# Force.net
KiCad netlist of a schematic drawn in Altium Designer
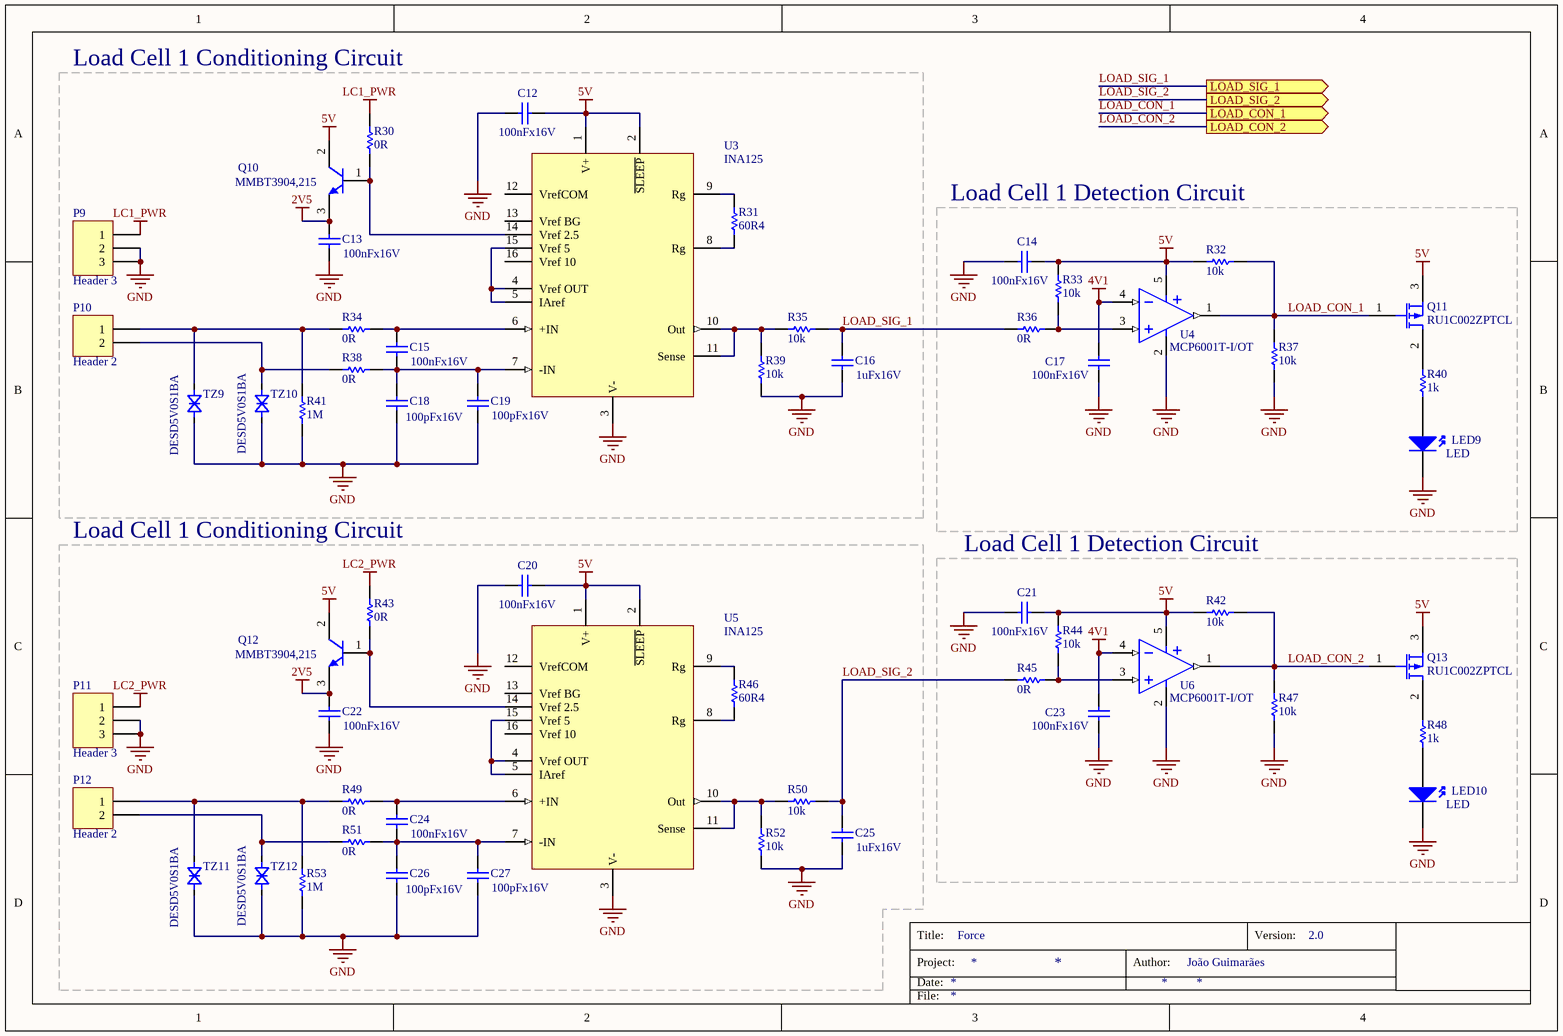
[diagram p0: Force.SchDoc]

(export (version "E")
  (design (tool "Eeschema 10.0.6"))
  (components
    (comp (ref "C12")
      (value "100nFx16V")
      (footprint "DISC-0805")
      (description "Capacitor")
      (libsource (lib "IntLib") (part "Cap"))
    )
    (comp (ref "C13")
      (value "100nFx16V")
      (footprint "DISC-0805")
      (description "Capacitor")
      (libsource (lib "IntLib") (part "Cap"))
    )
    (comp (ref "C14")
      (value "100nFx16V")
      (footprint "DISC-0805")
      (description "Capacitor")
      (libsource (lib "IntLib") (part "Cap"))
    )
    (comp (ref "C15")
      (value "100nFx16V")
      (footprint "DISC-0805")
      (description "Capacitor")
      (libsource (lib "IntLib") (part "Cap"))
    )
    (comp (ref "C16")
      (value "1uFx16V")
      (footprint "DISC-0805")
      (description "Capacitor")
      (libsource (lib "IntLib") (part "Cap"))
    )
    (comp (ref "C17")
      (value "100nFx16V")
      (footprint "DISC-0805")
      (description "Capacitor")
      (libsource (lib "IntLib") (part "Cap"))
    )
    (comp (ref "C18")
      (value "100pFx16V")
      (footprint "DISC-0805")
      (description "Capacitor")
      (libsource (lib "IntLib") (part "Cap"))
    )
    (comp (ref "C19")
      (value "100pFx16V")
      (footprint "DISC-0805")
      (description "Capacitor")
      (libsource (lib "IntLib") (part "Cap"))
    )
    (comp (ref "C20")
      (value "100nFx16V")
      (footprint "DISC-0805")
      (description "Capacitor")
      (libsource (lib "IntLib") (part "Cap"))
    )
    (comp (ref "C21")
      (value "100nFx16V")
      (footprint "DISC-0805")
      (description "Capacitor")
      (libsource (lib "IntLib") (part "Cap"))
    )
    (comp (ref "C22")
      (value "100nFx16V")
      (footprint "DISC-0805")
      (description "Capacitor")
      (libsource (lib "IntLib") (part "Cap"))
    )
    (comp (ref "C23")
      (value "100nFx16V")
      (footprint "DISC-0805")
      (description "Capacitor")
      (libsource (lib "IntLib") (part "Cap"))
    )
    (comp (ref "C24")
      (value "100nFx16V")
      (footprint "DISC-0805")
      (description "Capacitor")
      (libsource (lib "IntLib") (part "Cap"))
    )
    (comp (ref "C25")
      (value "1uFx16V")
      (footprint "DISC-0805")
      (description "Capacitor")
      (libsource (lib "IntLib") (part "Cap"))
    )
    (comp (ref "C26")
      (value "100pFx16V")
      (footprint "DISC-0805")
      (description "Capacitor")
      (libsource (lib "IntLib") (part "Cap"))
    )
    (comp (ref "C27")
      (value "100pFx16V")
      (footprint "DISC-0805")
      (description "Capacitor")
      (libsource (lib "IntLib") (part "Cap"))
    )
    (comp (ref "LED9") (value "LED") (footprint "DISC-LED-0.1-PTH") (libsource (lib "IntLib") (part "LED")))
    (comp (ref "LED10") (value "LED") (footprint "DISC-LED-0.1-PTH") (libsource (lib "IntLib") (part "LED")))
    (comp (ref "P9")
      (value "Header 3")
      (footprint "CON-FLEXWIRE-0.5MM2-1X3")
      (description "Header, 3-Pin")
      (fields (field (name "PUBLISHER") "Altium Limited"))
      (libsource (lib "IntLib") (part "Header 3"))
    )
    (comp (ref "P10")
      (value "Header 2")
      (footprint "CON-BORNE-2")
      (description "Header, 2-Pin")
      (fields (field (name "PUBLISHER") "Altium Limited"))
      (libsource (lib "IntLib") (part "Header 2"))
    )
    (comp (ref "P11")
      (value "Header 3")
      (footprint "CON-FLEXWIRE-0.5MM2-1X3")
      (description "Header, 3-Pin")
      (fields (field (name "PUBLISHER") "Altium Limited"))
      (libsource (lib "IntLib") (part "Header 3"))
    )
    (comp (ref "P12")
      (value "Header 2")
      (footprint "CON-BORNE-2")
      (description "Header, 2-Pin")
      (fields (field (name "PUBLISHER") "Altium Limited"))
      (libsource (lib "IntLib") (part "Header 2"))
    )
    (comp (ref "Q10")
      (value "MMBT3904,215")
      (footprint "DISC-SOT-23")
      (description "NPN Bipolar Transistor")
      (fields (field (name "PUBLISHER") "Altium Limited"))
      (libsource (lib "IntLib") (part "Transistor-NPN"))
    )
    (comp (ref "Q11")
      (value "RU1C002ZPTCL")
      (footprint "DISC-SOT-23")
      (description "P-Channel MOSFET")
      (libsource (lib "IntLib") (part "Transistor-PMOS"))
    )
    (comp (ref "Q12")
      (value "MMBT3904,215")
      (footprint "DISC-SOT-23")
      (description "NPN Bipolar Transistor")
      (fields (field (name "PUBLISHER") "Altium Limited"))
      (libsource (lib "IntLib") (part "Transistor-NPN"))
    )
    (comp (ref "Q13")
      (value "RU1C002ZPTCL")
      (footprint "DISC-SOT-23")
      (description "P-Channel MOSFET")
      (libsource (lib "IntLib") (part "Transistor-PMOS"))
    )
    (comp (ref "R30")
      (value "0R")
      (footprint "DISC-0805")
      (description "Resistor")
      (libsource (lib "IntLib") (part "Res"))
    )
    (comp (ref "R31")
      (value "60R4")
      (footprint "DISC-0805")
      (description "Resistor")
      (libsource (lib "IntLib") (part "Res"))
    )
    (comp (ref "R32")
      (value "10k")
      (footprint "DISC-0805")
      (description "Resistor")
      (libsource (lib "IntLib") (part "Res"))
    )
    (comp (ref "R33")
      (value "10k")
      (footprint "DISC-0805")
      (description "Resistor")
      (libsource (lib "IntLib") (part "Res"))
    )
    (comp (ref "R34")
      (value "0R")
      (footprint "DISC-0805")
      (description "Resistor")
      (libsource (lib "IntLib") (part "Res"))
    )
    (comp (ref "R35")
      (value "10k")
      (footprint "DISC-0805")
      (description "Resistor")
      (libsource (lib "IntLib") (part "Res"))
    )
    (comp (ref "R36")
      (value "0R")
      (footprint "DISC-0805")
      (description "Resistor")
      (libsource (lib "IntLib") (part "Res"))
    )
    (comp (ref "R37")
      (value "10k")
      (footprint "DISC-0805")
      (description "Resistor")
      (libsource (lib "IntLib") (part "Res"))
    )
    (comp (ref "R38")
      (value "0R")
      (footprint "DISC-0805")
      (description "Resistor")
      (libsource (lib "IntLib") (part "Res"))
    )
    (comp (ref "R39")
      (value "10k")
      (footprint "DISC-0805")
      (description "Resistor")
      (libsource (lib "IntLib") (part "Res"))
    )
    (comp (ref "R40")
      (value "1k")
      (footprint "DISC-0805")
      (description "Resistor")
      (libsource (lib "IntLib") (part "Res"))
    )
    (comp (ref "R41")
      (value "1M")
      (footprint "DISC-0805")
      (description "Resistor")
      (libsource (lib "IntLib") (part "Res"))
    )
    (comp (ref "R42")
      (value "10k")
      (footprint "DISC-0805")
      (description "Resistor")
      (libsource (lib "IntLib") (part "Res"))
    )
    (comp (ref "R43")
      (value "0R")
      (footprint "DISC-0805")
      (description "Resistor")
      (libsource (lib "IntLib") (part "Res"))
    )
    (comp (ref "R44")
      (value "10k")
      (footprint "DISC-0805")
      (description "Resistor")
      (libsource (lib "IntLib") (part "Res"))
    )
    (comp (ref "R45")
      (value "0R")
      (footprint "DISC-0805")
      (description "Resistor")
      (libsource (lib "IntLib") (part "Res"))
    )
    (comp (ref "R46")
      (value "60R4")
      (footprint "DISC-0805")
      (description "Resistor")
      (libsource (lib "IntLib") (part "Res"))
    )
    (comp (ref "R47")
      (value "10k")
      (footprint "DISC-0805")
      (description "Resistor")
      (libsource (lib "IntLib") (part "Res"))
    )
    (comp (ref "R48")
      (value "1k")
      (footprint "DISC-0805")
      (description "Resistor")
      (libsource (lib "IntLib") (part "Res"))
    )
    (comp (ref "R49")
      (value "0R")
      (footprint "DISC-0805")
      (description "Resistor")
      (libsource (lib "IntLib") (part "Res"))
    )
    (comp (ref "R50")
      (value "10k")
      (footprint "DISC-0805")
      (description "Resistor")
      (libsource (lib "IntLib") (part "Res"))
    )
    (comp (ref "R51")
      (value "0R")
      (footprint "DISC-0805")
      (description "Resistor")
      (libsource (lib "IntLib") (part "Res"))
    )
    (comp (ref "R52")
      (value "10k")
      (footprint "DISC-0805")
      (description "Resistor")
      (libsource (lib "IntLib") (part "Res"))
    )
    (comp (ref "R53")
      (value "1M")
      (footprint "DISC-0805")
      (description "Resistor")
      (libsource (lib "IntLib") (part "Res"))
    )
    (comp (ref "TZ9")
      (value "DESD5V0S1BA")
      (footprint "DISC-SOD-323")
      (description "TVZ-Bi-Directional")
      (libsource (lib "IntLib") (part "TVZ-Bi-Directional"))
    )
    (comp (ref "TZ10")
      (value "DESD5V0S1BA")
      (footprint "DISC-SOD-323")
      (description "TVZ-Bi-Directional")
      (libsource (lib "IntLib") (part "TVZ-Bi-Directional"))
    )
    (comp (ref "TZ11")
      (value "DESD5V0S1BA")
      (footprint "DISC-SOD-323")
      (description "TVZ-Bi-Directional")
      (libsource (lib "IntLib") (part "TVZ-Bi-Directional"))
    )
    (comp (ref "TZ12")
      (value "DESD5V0S1BA")
      (footprint "DISC-SOD-323")
      (description "TVZ-Bi-Directional")
      (libsource (lib "IntLib") (part "TVZ-Bi-Directional"))
    )
    (comp (ref "U3")
      (value "INA125")
      (footprint "CI-SOIC-16")
      (description "INSTRUMENTATION AMPLIFIER With Precision Voltage Reference")
      (libsource (lib "IntLib") (part "INA125P"))
    )
    (comp (ref "U4")
      (value "MCP6001T-I/OT")
      (footprint "CI-SOT-23-5")
      (description "Operational Amplifiers - Op Amps Single 1.8V 1MHz")
      (libsource (lib "IntLib") (part "MCP6001T-I/OT"))
    )
    (comp (ref "U5")
      (value "INA125")
      (footprint "CI-SOIC-16")
      (description "INSTRUMENTATION AMPLIFIER With Precision Voltage Reference")
      (libsource (lib "IntLib") (part "INA125P"))
    )
    (comp (ref "U6")
      (value "MCP6001T-I/OT")
      (footprint "CI-SOT-23-5")
      (description "Operational Amplifiers - Op Amps Single 1.8V 1MHz")
      (libsource (lib "IntLib") (part "MCP6001T-I/OT"))
    )
  )
  (nets
    (net (code "1") (name "/LOAD_CON_1") (class "Default")
      (node (ref "Q11") (pin "1") (pinfunction "G_1") (pintype "passive"))
      (node (ref "R32") (pin "2") (pinfunction "2_2") (pintype "passive"))
      (node (ref "R37") (pin "1") (pinfunction "1_1") (pintype "passive"))
      (node (ref "U4") (pin "1") (pinfunction "Out_1") (pintype "output"))
    )
    (net (code "2") (name "/LOAD_CON_2") (class "Default")
      (node (ref "Q13") (pin "1") (pinfunction "G_1") (pintype "passive"))
      (node (ref "R42") (pin "2") (pinfunction "2_2") (pintype "passive"))
      (node (ref "R47") (pin "1") (pinfunction "1_1") (pintype "passive"))
      (node (ref "U6") (pin "1") (pinfunction "Out_1") (pintype "output"))
    )
    (net (code "3") (name "/LOAD_SIG_1") (class "Default")
      (node (ref "C16") (pin "2") (pinfunction "2_2") (pintype "passive"))
      (node (ref "R35") (pin "2") (pinfunction "2_2") (pintype "passive"))
      (node (ref "R36") (pin "1") (pinfunction "1_1") (pintype "passive"))
    )
    (net (code "4") (name "/LOAD_SIG_2") (class "Default")
      (node (ref "C25") (pin "2") (pinfunction "2_2") (pintype "passive"))
      (node (ref "R45") (pin "1") (pinfunction "1_1") (pintype "passive"))
      (node (ref "R50") (pin "2") (pinfunction "2_2") (pintype "passive"))
    )
    (net (code "5") (name "2V5") (class "Default")
      (node (ref "C13") (pin "2") (pinfunction "2_2") (pintype "passive"))
      (node (ref "C22") (pin "2") (pinfunction "2_2") (pintype "passive"))
      (node (ref "Q10") (pin "3") (pinfunction "E_3") (pintype "passive"))
      (node (ref "Q12") (pin "3") (pinfunction "E_3") (pintype "passive"))
    )
    (net (code "6") (name "4V1") (class "Default")
      (node (ref "C17") (pin "2") (pinfunction "2_2") (pintype "passive"))
      (node (ref "C23") (pin "2") (pinfunction "2_2") (pintype "passive"))
      (node (ref "U4") (pin "4") (pinfunction "IN-_4") (pintype "input"))
      (node (ref "U6") (pin "4") (pinfunction "IN-_4") (pintype "input"))
    )
    (net (code "7") (name "5V") (class "Default")
      (node (ref "C12") (pin "1") (pinfunction "1_1") (pintype "passive"))
      (node (ref "C14") (pin "2") (pinfunction "2_2") (pintype "passive"))
      (node (ref "C20") (pin "1") (pinfunction "1_1") (pintype "passive"))
      (node (ref "C21") (pin "2") (pinfunction "2_2") (pintype "passive"))
      (node (ref "Q10") (pin "2") (pinfunction "C_2") (pintype "passive"))
      (node (ref "Q11") (pin "3") (pinfunction "S_3") (pintype "passive"))
      (node (ref "Q12") (pin "2") (pinfunction "C_2") (pintype "passive"))
      (node (ref "Q13") (pin "3") (pinfunction "S_3") (pintype "passive"))
      (node (ref "R32") (pin "1") (pinfunction "1_1") (pintype "passive"))
      (node (ref "R33") (pin "1") (pinfunction "1_1") (pintype "passive"))
      (node (ref "R42") (pin "1") (pinfunction "1_1") (pintype "passive"))
      (node (ref "R44") (pin "1") (pinfunction "1_1") (pintype "passive"))
      (node (ref "U3") (pin "1") (pinfunction "V+_1") (pintype "power_in"))
      (node (ref "U3") (pin "2") (pinfunction "~{SLEEP}_2") (pintype "passive"))
      (node (ref "U4") (pin "5") (pinfunction "V+_5") (pintype "power_in"))
      (node (ref "U5") (pin "1") (pinfunction "V+_1") (pintype "power_in"))
      (node (ref "U5") (pin "2") (pinfunction "~{SLEEP}_2") (pintype "passive"))
      (node (ref "U6") (pin "5") (pinfunction "V+_5") (pintype "power_in"))
    )
    (net (code "8") (name "GND") (class "Default")
      (node (ref "C12") (pin "2") (pinfunction "2_2") (pintype "passive"))
      (node (ref "C13") (pin "1") (pinfunction "1_1") (pintype "passive"))
      (node (ref "C14") (pin "1") (pinfunction "1_1") (pintype "passive"))
      (node (ref "C16") (pin "1") (pinfunction "1_1") (pintype "passive"))
      (node (ref "C17") (pin "1") (pinfunction "1_1") (pintype "passive"))
      (node (ref "C18") (pin "1") (pinfunction "1_1") (pintype "passive"))
      (node (ref "C19") (pin "1") (pinfunction "1_1") (pintype "passive"))
      (node (ref "C20") (pin "2") (pinfunction "2_2") (pintype "passive"))
      (node (ref "C21") (pin "1") (pinfunction "1_1") (pintype "passive"))
      (node (ref "C22") (pin "1") (pinfunction "1_1") (pintype "passive"))
      (node (ref "C23") (pin "1") (pinfunction "1_1") (pintype "passive"))
      (node (ref "C25") (pin "1") (pinfunction "1_1") (pintype "passive"))
      (node (ref "C26") (pin "1") (pinfunction "1_1") (pintype "passive"))
      (node (ref "C27") (pin "1") (pinfunction "1_1") (pintype "passive"))
      (node (ref "LED10") (pin "2") (pinfunction "K_2") (pintype "passive"))
      (node (ref "LED9") (pin "2") (pinfunction "K_2") (pintype "passive"))
      (node (ref "P11") (pin "2") (pinfunction "2_2") (pintype "passive"))
      (node (ref "P11") (pin "3") (pinfunction "3_3") (pintype "passive"))
      (node (ref "P9") (pin "2") (pinfunction "2_2") (pintype "passive"))
      (node (ref "P9") (pin "3") (pinfunction "3_3") (pintype "passive"))
      (node (ref "R37") (pin "2") (pinfunction "2_2") (pintype "passive"))
      (node (ref "R39") (pin "2") (pinfunction "2_2") (pintype "passive"))
      (node (ref "R41") (pin "1") (pinfunction "1_1") (pintype "passive"))
      (node (ref "R47") (pin "2") (pinfunction "2_2") (pintype "passive"))
      (node (ref "R52") (pin "2") (pinfunction "2_2") (pintype "passive"))
      (node (ref "R53") (pin "1") (pinfunction "1_1") (pintype "passive"))
      (node (ref "TZ10") (pin "1") (pinfunction "A_1") (pintype "passive"))
      (node (ref "TZ11") (pin "1") (pinfunction "A_1") (pintype "passive"))
      (node (ref "TZ12") (pin "1") (pinfunction "A_1") (pintype "passive"))
      (node (ref "TZ9") (pin "1") (pinfunction "A_1") (pintype "passive"))
      (node (ref "U3") (pin "3") (pinfunction "V-_3") (pintype "power_in"))
      (node (ref "U4") (pin "2") (pinfunction "V-_2") (pintype "power_in"))
      (node (ref "U5") (pin "3") (pinfunction "V-_3") (pintype "power_in"))
      (node (ref "U6") (pin "2") (pinfunction "V-_2") (pintype "power_in"))
    )
    (net (code "9") (name "LC1_PWR") (class "Default")
      (node (ref "P9") (pin "1") (pinfunction "1_1") (pintype "passive"))
      (node (ref "R30") (pin "1") (pinfunction "1_1") (pintype "passive"))
    )
    (net (code "10") (name "LC2_PWR") (class "Default")
      (node (ref "P11") (pin "1") (pinfunction "1_1") (pintype "passive"))
      (node (ref "R43") (pin "1") (pinfunction "1_1") (pintype "passive"))
    )
    (net (code "11") (name "Net-(LED9-A)") (class "Default")
      (node (ref "LED9") (pin "1") (pinfunction "A_1") (pintype "passive"))
      (node (ref "R40") (pin "1") (pinfunction "1_1") (pintype "passive"))
    )
    (net (code "12") (name "Net-(LED10-A)") (class "Default")
      (node (ref "LED10") (pin "1") (pinfunction "A_1") (pintype "passive"))
      (node (ref "R48") (pin "1") (pinfunction "1_1") (pintype "passive"))
    )
    (net (code "13") (name "Net-(Q10-B)") (class "Default")
      (node (ref "Q10") (pin "1") (pinfunction "B_1") (pintype "passive"))
      (node (ref "R30") (pin "2") (pinfunction "2_2") (pintype "passive"))
      (node (ref "U3") (pin "14") (pinfunction "Vref_2.5_14") (pintype "passive"))
    )
    (net (code "14") (name "Net-(Q11-D)") (class "Default")
      (node (ref "Q11") (pin "2") (pinfunction "D_2") (pintype "passive"))
      (node (ref "R40") (pin "2") (pinfunction "2_2") (pintype "passive"))
    )
    (net (code "15") (name "Net-(Q12-B)") (class "Default")
      (node (ref "Q12") (pin "1") (pinfunction "B_1") (pintype "passive"))
      (node (ref "R43") (pin "2") (pinfunction "2_2") (pintype "passive"))
      (node (ref "U5") (pin "14") (pinfunction "Vref_2.5_14") (pintype "passive"))
    )
    (net (code "16") (name "Net-(Q13-D)") (class "Default")
      (node (ref "Q13") (pin "2") (pinfunction "D_2") (pintype "passive"))
      (node (ref "R48") (pin "2") (pinfunction "2_2") (pintype "passive"))
    )
    (net (code "17") (name "Net-(R31-Pad1)") (class "Default")
      (node (ref "R31") (pin "1") (pinfunction "1_1") (pintype "passive"))
      (node (ref "U3") (pin "9") (pinfunction "Rg_9") (pintype "passive"))
    )
    (net (code "18") (name "Net-(R31-Pad2)") (class "Default")
      (node (ref "R31") (pin "2") (pinfunction "2_2") (pintype "passive"))
      (node (ref "U3") (pin "8") (pinfunction "Rg_8") (pintype "passive"))
    )
    (net (code "19") (name "Net-(R46-Pad1)") (class "Default")
      (node (ref "R46") (pin "1") (pinfunction "1_1") (pintype "passive"))
      (node (ref "U5") (pin "9") (pinfunction "Rg_9") (pintype "passive"))
    )
    (net (code "20") (name "Net-(R46-Pad2)") (class "Default")
      (node (ref "R46") (pin "2") (pinfunction "2_2") (pintype "passive"))
      (node (ref "U5") (pin "8") (pinfunction "Rg_8") (pintype "passive"))
    )
    (net (code "21") (name "Net-(TZ9-K)") (class "Default")
      (node (ref "P10") (pin "1") (pinfunction "1_1") (pintype "passive"))
      (node (ref "R34") (pin "2") (pinfunction "2_2") (pintype "passive"))
      (node (ref "R41") (pin "2") (pinfunction "2_2") (pintype "passive"))
      (node (ref "TZ9") (pin "2") (pinfunction "K_2") (pintype "passive"))
    )
    (net (code "22") (name "Net-(TZ10-K)") (class "Default")
      (node (ref "P10") (pin "2") (pinfunction "2_2") (pintype "passive"))
      (node (ref "R38") (pin "2") (pinfunction "2_2") (pintype "passive"))
      (node (ref "TZ10") (pin "2") (pinfunction "K_2") (pintype "passive"))
    )
    (net (code "23") (name "Net-(TZ11-K)") (class "Default")
      (node (ref "P12") (pin "1") (pinfunction "1_1") (pintype "passive"))
      (node (ref "R49") (pin "2") (pinfunction "2_2") (pintype "passive"))
      (node (ref "R53") (pin "2") (pinfunction "2_2") (pintype "passive"))
      (node (ref "TZ11") (pin "2") (pinfunction "K_2") (pintype "passive"))
    )
    (net (code "24") (name "Net-(TZ12-K)") (class "Default")
      (node (ref "P12") (pin "2") (pinfunction "2_2") (pintype "passive"))
      (node (ref "R51") (pin "2") (pinfunction "2_2") (pintype "passive"))
      (node (ref "TZ12") (pin "2") (pinfunction "K_2") (pintype "passive"))
    )
    (net (code "25") (name "Net-(U3-+IN)") (class "Default")
      (node (ref "C15") (pin "2") (pinfunction "2_2") (pintype "passive"))
      (node (ref "R34") (pin "1") (pinfunction "1_1") (pintype "passive"))
      (node (ref "U3") (pin "6") (pinfunction "+IN_6") (pintype "input"))
    )
    (net (code "26") (name "Net-(U3--IN)") (class "Default")
      (node (ref "C15") (pin "1") (pinfunction "1_1") (pintype "passive"))
      (node (ref "C18") (pin "2") (pinfunction "2_2") (pintype "passive"))
      (node (ref "C19") (pin "2") (pinfunction "2_2") (pintype "passive"))
      (node (ref "R38") (pin "1") (pinfunction "1_1") (pintype "passive"))
      (node (ref "U3") (pin "7") (pinfunction "-IN_7") (pintype "input"))
    )
    (net (code "27") (name "Net-(U3-IAref)") (class "Default")
      (node (ref "U3") (pin "15") (pinfunction "Vref_5_15") (pintype "passive"))
      (node (ref "U3") (pin "4") (pinfunction "Vref_OUT_4") (pintype "passive"))
      (node (ref "U3") (pin "5") (pinfunction "IAref_5") (pintype "passive"))
    )
    (net (code "28") (name "Net-(U3-Out)") (class "Default")
      (node (ref "R35") (pin "1") (pinfunction "1_1") (pintype "passive"))
      (node (ref "R39") (pin "1") (pinfunction "1_1") (pintype "passive"))
      (node (ref "U3") (pin "10") (pinfunction "Out_10") (pintype "output"))
      (node (ref "U3") (pin "11") (pinfunction "Sense_11") (pintype "passive"))
    )
    (net (code "29") (name "Net-(U4-IN+)") (class "Default")
      (node (ref "R33") (pin "2") (pinfunction "2_2") (pintype "passive"))
      (node (ref "R36") (pin "2") (pinfunction "2_2") (pintype "passive"))
      (node (ref "U4") (pin "3") (pinfunction "IN+_3") (pintype "input"))
    )
    (net (code "30") (name "Net-(U5-+IN)") (class "Default")
      (node (ref "C24") (pin "2") (pinfunction "2_2") (pintype "passive"))
      (node (ref "R49") (pin "1") (pinfunction "1_1") (pintype "passive"))
      (node (ref "U5") (pin "6") (pinfunction "+IN_6") (pintype "input"))
    )
    (net (code "31") (name "Net-(U5--IN)") (class "Default")
      (node (ref "C24") (pin "1") (pinfunction "1_1") (pintype "passive"))
      (node (ref "C26") (pin "2") (pinfunction "2_2") (pintype "passive"))
      (node (ref "C27") (pin "2") (pinfunction "2_2") (pintype "passive"))
      (node (ref "R51") (pin "1") (pinfunction "1_1") (pintype "passive"))
      (node (ref "U5") (pin "7") (pinfunction "-IN_7") (pintype "input"))
    )
    (net (code "32") (name "Net-(U5-IAref)") (class "Default")
      (node (ref "U5") (pin "15") (pinfunction "Vref_5_15") (pintype "passive"))
      (node (ref "U5") (pin "4") (pinfunction "Vref_OUT_4") (pintype "passive"))
      (node (ref "U5") (pin "5") (pinfunction "IAref_5") (pintype "passive"))
    )
    (net (code "33") (name "Net-(U5-Out)") (class "Default")
      (node (ref "R50") (pin "1") (pinfunction "1_1") (pintype "passive"))
      (node (ref "R52") (pin "1") (pinfunction "1_1") (pintype "passive"))
      (node (ref "U5") (pin "10") (pinfunction "Out_10") (pintype "output"))
      (node (ref "U5") (pin "11") (pinfunction "Sense_11") (pintype "passive"))
    )
    (net (code "34") (name "Net-(U6-IN+)") (class "Default")
      (node (ref "R44") (pin "2") (pinfunction "2_2") (pintype "passive"))
      (node (ref "R45") (pin "2") (pinfunction "2_2") (pintype "passive"))
      (node (ref "U6") (pin "3") (pinfunction "IN+_3") (pintype "input"))
    )
    (net (code "35") (name "unconnected-(U3-VrefCOM-Pad12)") (class "Default")
      (node (ref "U3") (pin "12") (pinfunction "VrefCOM_12") (pintype "passive"))
    )
    (net (code "36") (name "unconnected-(U3-Vref_10-Pad16)") (class "Default")
      (node (ref "U3") (pin "16") (pinfunction "Vref_10_16") (pintype "passive"))
    )
    (net (code "37") (name "unconnected-(U3-Vref_BG-Pad13)") (class "Default")
      (node (ref "U3") (pin "13") (pinfunction "Vref_BG_13") (pintype "passive"))
    )
    (net (code "38") (name "unconnected-(U5-VrefCOM-Pad12)") (class "Default")
      (node (ref "U5") (pin "12") (pinfunction "VrefCOM_12") (pintype "passive"))
    )
    (net (code "39") (name "unconnected-(U5-Vref_10-Pad16)") (class "Default")
      (node (ref "U5") (pin "16") (pinfunction "Vref_10_16") (pintype "passive"))
    )
    (net (code "40") (name "unconnected-(U5-Vref_BG-Pad13)") (class "Default")
      (node (ref "U5") (pin "13") (pinfunction "Vref_BG_13") (pintype "passive"))
    )
  )
)
